# TempPCB_v18.net
KiCad netlist of a schematic drawn in EAGLE
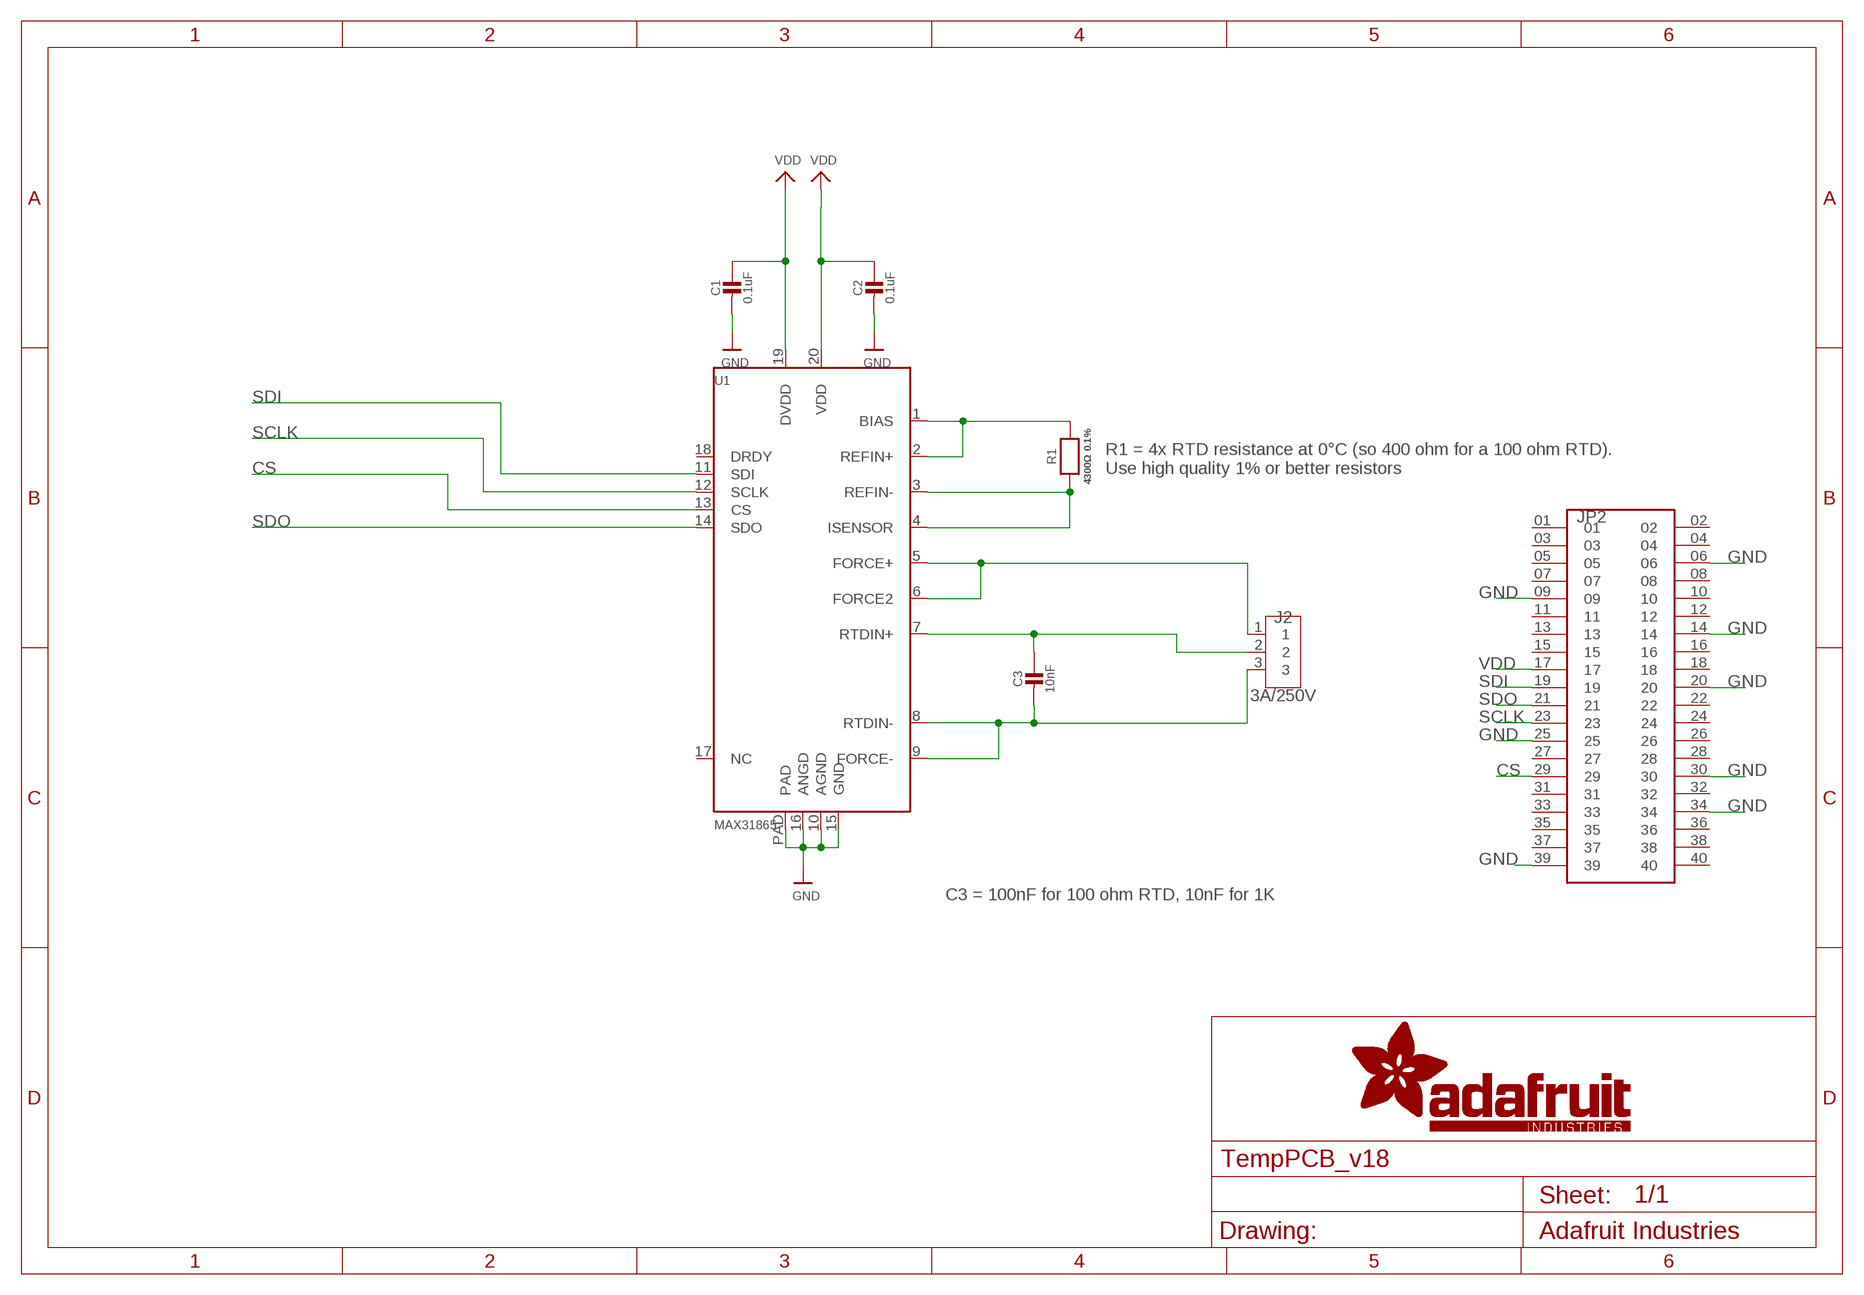
[diagram p0: schematic, sheet 1]

(export (version "E")
  (design (tool "Eeschema 10.0.6"))
  (components
    (comp (ref "C1")
      (value "0.1uF")
      (footprint "eagle-import:0805-NO")
      (libsource (lib "eagle-import") (part "CAP_CERAMIC0805-NOOUTLINE"))
    )
    (comp (ref "C2")
      (value "0.1uF")
      (footprint "eagle-import:0805-NO")
      (libsource (lib "eagle-import") (part "CAP_CERAMIC0805-NOOUTLINE"))
    )
    (comp (ref "C3")
      (value "10nF")
      (footprint "eagle-import:0805-NO")
      (libsource (lib "eagle-import") (part "CAP_CERAMIC0805-NOOUTLINE"))
    )
    (comp (ref "J2")
      (value "3A/250V")
      (footprint "eagle-import:S3B-XH-A")
      (fields
        (field (name "MANUFACTURER") "JST Sales America Inc. ")
        (field (name "MPN") "S3B-XH-A(LF)(SN) ")
      )
      (libsource (lib "eagle-import") (part "S3B-XH-A"))
    )
    (comp (ref "JP2")
      (value "SSQ-120-03-T-D")
      (footprint "eagle-import:SAMTEC_SSQ-120-03-T-D")
      (fields (field (name "MANUFACTURER") "Samtec Inc."))
      (libsource (lib "eagle-import") (part "SSQ-120-03-T-D"))
    )
    (comp (ref "R1")
      (value "4300Ω 0.1%")
      (footprint "eagle-import:0805-NO")
      (libsource (lib "eagle-import") (part "RESISTOR0805_NOOUTLINE"))
    )
    (comp (ref "U1")
      (value "MAX31865")
      (footprint "eagle-import:QFN20_4MM_0.65MM")
      (libsource (lib "eagle-import") (part "TEMP_MAX31865"))
    )
  )
  (nets
    (net (code "1") (name "/CS") (class "Default")
      (node (ref "JP2") (pin "29") (pinfunction "29_29") (pintype "passive"))
      (node (ref "U1") (pin "13") (pinfunction "CS_13") (pintype "input"))
    )
    (net (code "2") (name "/SCLK") (class "Default")
      (node (ref "JP2") (pin "23") (pinfunction "23_23") (pintype "passive"))
      (node (ref "U1") (pin "12") (pinfunction "SCLK_12") (pintype "input"))
    )
    (net (code "3") (name "/SDI") (class "Default")
      (node (ref "JP2") (pin "19") (pinfunction "19_19") (pintype "passive"))
      (node (ref "U1") (pin "11") (pinfunction "SDI_11") (pintype "input"))
    )
    (net (code "4") (name "/SDO") (class "Default")
      (node (ref "JP2") (pin "21") (pinfunction "21_21") (pintype "passive"))
      (node (ref "U1") (pin "14") (pinfunction "SDO_14") (pintype "output"))
    )
    (net (code "5") (name "GND") (class "Default")
      (node (ref "C1") (pin "2") (pinfunction "2_2") (pintype "passive"))
      (node (ref "C2") (pin "2") (pinfunction "2_2") (pintype "passive"))
      (node (ref "JP2") (pin "06") (pinfunction "06_06") (pintype "passive"))
      (node (ref "JP2") (pin "09") (pinfunction "09_09") (pintype "passive"))
      (node (ref "JP2") (pin "14") (pinfunction "14_14") (pintype "passive"))
      (node (ref "JP2") (pin "20") (pinfunction "20_20") (pintype "passive"))
      (node (ref "JP2") (pin "25") (pinfunction "25_25") (pintype "passive"))
      (node (ref "JP2") (pin "30") (pinfunction "30_30") (pintype "passive"))
      (node (ref "JP2") (pin "34") (pinfunction "34_34") (pintype "passive"))
      (node (ref "JP2") (pin "39") (pinfunction "39_39") (pintype "passive"))
      (node (ref "U1") (pin "10") (pinfunction "AGND_10") (pintype "power_in"))
      (node (ref "U1") (pin "15") (pinfunction "GND_15") (pintype "power_in"))
      (node (ref "U1") (pin "16") (pinfunction "ANGD_16") (pintype "power_in"))
      (node (ref "U1") (pin "PAD") (pinfunction "PAD_PAD") (pintype "power_in"))
    )
    (net (code "6") (name "Net-(U1-BIAS)") (class "Default")
      (node (ref "R1") (pin "2") (pinfunction "2_2") (pintype "passive"))
      (node (ref "U1") (pin "1") (pinfunction "BIAS_1") (pintype "output"))
      (node (ref "U1") (pin "2") (pinfunction "REFIN+_2") (pintype "bidirectional"))
    )
    (net (code "7") (name "Net-(U1-FORCE+)") (class "Default")
      (node (ref "J2") (pin "1") (pinfunction "1_1") (pintype "bidirectional"))
      (node (ref "U1") (pin "5") (pinfunction "FORCE+_5") (pintype "output"))
      (node (ref "U1") (pin "6") (pinfunction "FORCE2_6") (pintype "bidirectional"))
    )
    (net (code "8") (name "Net-(U1-FORCE-)") (class "Default")
      (node (ref "C3") (pin "2") (pinfunction "2_2") (pintype "passive"))
      (node (ref "J2") (pin "3") (pinfunction "3_3") (pintype "bidirectional"))
      (node (ref "U1") (pin "8") (pinfunction "RTDIN-_8") (pintype "bidirectional"))
      (node (ref "U1") (pin "9") (pinfunction "FORCE-_9") (pintype "input"))
    )
    (net (code "9") (name "Net-(U1-ISENSOR)") (class "Default")
      (node (ref "R1") (pin "1") (pinfunction "1_1") (pintype "passive"))
      (node (ref "U1") (pin "3") (pinfunction "REFIN-_3") (pintype "bidirectional"))
      (node (ref "U1") (pin "4") (pinfunction "ISENSOR_4") (pintype "input"))
    )
    (net (code "10") (name "Net-(U1-RTDIN+)") (class "Default")
      (node (ref "C3") (pin "1") (pinfunction "1_1") (pintype "passive"))
      (node (ref "J2") (pin "2") (pinfunction "2_2") (pintype "bidirectional"))
      (node (ref "U1") (pin "7") (pinfunction "RTDIN+_7") (pintype "bidirectional"))
    )
    (net (code "11") (name "VDD") (class "Default")
      (node (ref "C1") (pin "1") (pinfunction "1_1") (pintype "passive"))
      (node (ref "C2") (pin "1") (pinfunction "1_1") (pintype "passive"))
      (node (ref "JP2") (pin "17") (pinfunction "17_17") (pintype "passive"))
      (node (ref "U1") (pin "19") (pinfunction "DVDD_19") (pintype "power_in"))
      (node (ref "U1") (pin "20") (pinfunction "VDD_20") (pintype "power_in"))
    )
    (net (code "12") (name "unconnected-(JP2-Pad01)") (class "Default")
      (node (ref "JP2") (pin "01") (pinfunction "01_01") (pintype "passive"))
    )
    (net (code "13") (name "unconnected-(JP2-Pad02)") (class "Default")
      (node (ref "JP2") (pin "02") (pinfunction "02_02") (pintype "passive"))
    )
    (net (code "14") (name "unconnected-(JP2-Pad03)") (class "Default")
      (node (ref "JP2") (pin "03") (pinfunction "03_03") (pintype "passive"))
    )
    (net (code "15") (name "unconnected-(JP2-Pad04)") (class "Default")
      (node (ref "JP2") (pin "04") (pinfunction "04_04") (pintype "passive"))
    )
    (net (code "16") (name "unconnected-(JP2-Pad05)") (class "Default")
      (node (ref "JP2") (pin "05") (pinfunction "05_05") (pintype "passive"))
    )
    (net (code "17") (name "unconnected-(JP2-Pad07)") (class "Default")
      (node (ref "JP2") (pin "07") (pinfunction "07_07") (pintype "passive"))
    )
    (net (code "18") (name "unconnected-(JP2-Pad08)") (class "Default")
      (node (ref "JP2") (pin "08") (pinfunction "08_08") (pintype "passive"))
    )
    (net (code "19") (name "unconnected-(JP2-Pad10)") (class "Default")
      (node (ref "JP2") (pin "10") (pinfunction "10_10") (pintype "passive"))
    )
    (net (code "20") (name "unconnected-(JP2-Pad11)") (class "Default")
      (node (ref "JP2") (pin "11") (pinfunction "11_11") (pintype "passive"))
    )
    (net (code "21") (name "unconnected-(JP2-Pad12)") (class "Default")
      (node (ref "JP2") (pin "12") (pinfunction "12_12") (pintype "passive"))
    )
    (net (code "22") (name "unconnected-(JP2-Pad13)") (class "Default")
      (node (ref "JP2") (pin "13") (pinfunction "13_13") (pintype "passive"))
    )
    (net (code "23") (name "unconnected-(JP2-Pad15)") (class "Default")
      (node (ref "JP2") (pin "15") (pinfunction "15_15") (pintype "passive"))
    )
    (net (code "24") (name "unconnected-(JP2-Pad16)") (class "Default")
      (node (ref "JP2") (pin "16") (pinfunction "16_16") (pintype "passive"))
    )
    (net (code "25") (name "unconnected-(JP2-Pad18)") (class "Default")
      (node (ref "JP2") (pin "18") (pinfunction "18_18") (pintype "passive"))
    )
    (net (code "26") (name "unconnected-(JP2-Pad22)") (class "Default")
      (node (ref "JP2") (pin "22") (pinfunction "22_22") (pintype "passive"))
    )
    (net (code "27") (name "unconnected-(JP2-Pad24)") (class "Default")
      (node (ref "JP2") (pin "24") (pinfunction "24_24") (pintype "passive"))
    )
    (net (code "28") (name "unconnected-(JP2-Pad26)") (class "Default")
      (node (ref "JP2") (pin "26") (pinfunction "26_26") (pintype "passive"))
    )
    (net (code "29") (name "unconnected-(JP2-Pad27)") (class "Default")
      (node (ref "JP2") (pin "27") (pinfunction "27_27") (pintype "passive"))
    )
    (net (code "30") (name "unconnected-(JP2-Pad28)") (class "Default")
      (node (ref "JP2") (pin "28") (pinfunction "28_28") (pintype "passive"))
    )
    (net (code "31") (name "unconnected-(JP2-Pad31)") (class "Default")
      (node (ref "JP2") (pin "31") (pinfunction "31_31") (pintype "passive"))
    )
    (net (code "32") (name "unconnected-(JP2-Pad32)") (class "Default")
      (node (ref "JP2") (pin "32") (pinfunction "32_32") (pintype "passive"))
    )
    (net (code "33") (name "unconnected-(JP2-Pad33)") (class "Default")
      (node (ref "JP2") (pin "33") (pinfunction "33_33") (pintype "passive"))
    )
    (net (code "34") (name "unconnected-(JP2-Pad35)") (class "Default")
      (node (ref "JP2") (pin "35") (pinfunction "35_35") (pintype "passive"))
    )
    (net (code "35") (name "unconnected-(JP2-Pad36)") (class "Default")
      (node (ref "JP2") (pin "36") (pinfunction "36_36") (pintype "passive"))
    )
    (net (code "36") (name "unconnected-(JP2-Pad37)") (class "Default")
      (node (ref "JP2") (pin "37") (pinfunction "37_37") (pintype "passive"))
    )
    (net (code "37") (name "unconnected-(JP2-Pad38)") (class "Default")
      (node (ref "JP2") (pin "38") (pinfunction "38_38") (pintype "passive"))
    )
    (net (code "38") (name "unconnected-(JP2-Pad40)") (class "Default")
      (node (ref "JP2") (pin "40") (pinfunction "40_40") (pintype "passive"))
    )
    (net (code "39") (name "unconnected-(U1-DRDY-Pad18)") (class "Default")
      (node (ref "U1") (pin "18") (pinfunction "DRDY_18") (pintype "output"))
    )
    (net (code "40") (name "unconnected-(U1-NC-Pad17)") (class "Default")
      (node (ref "U1") (pin "17") (pinfunction "NC_17") (pintype "no_connect"))
    )
  )
)
